# 22_PHY_GE_PP1.net
KiCad netlist of a schematic drawn in Altium Designer
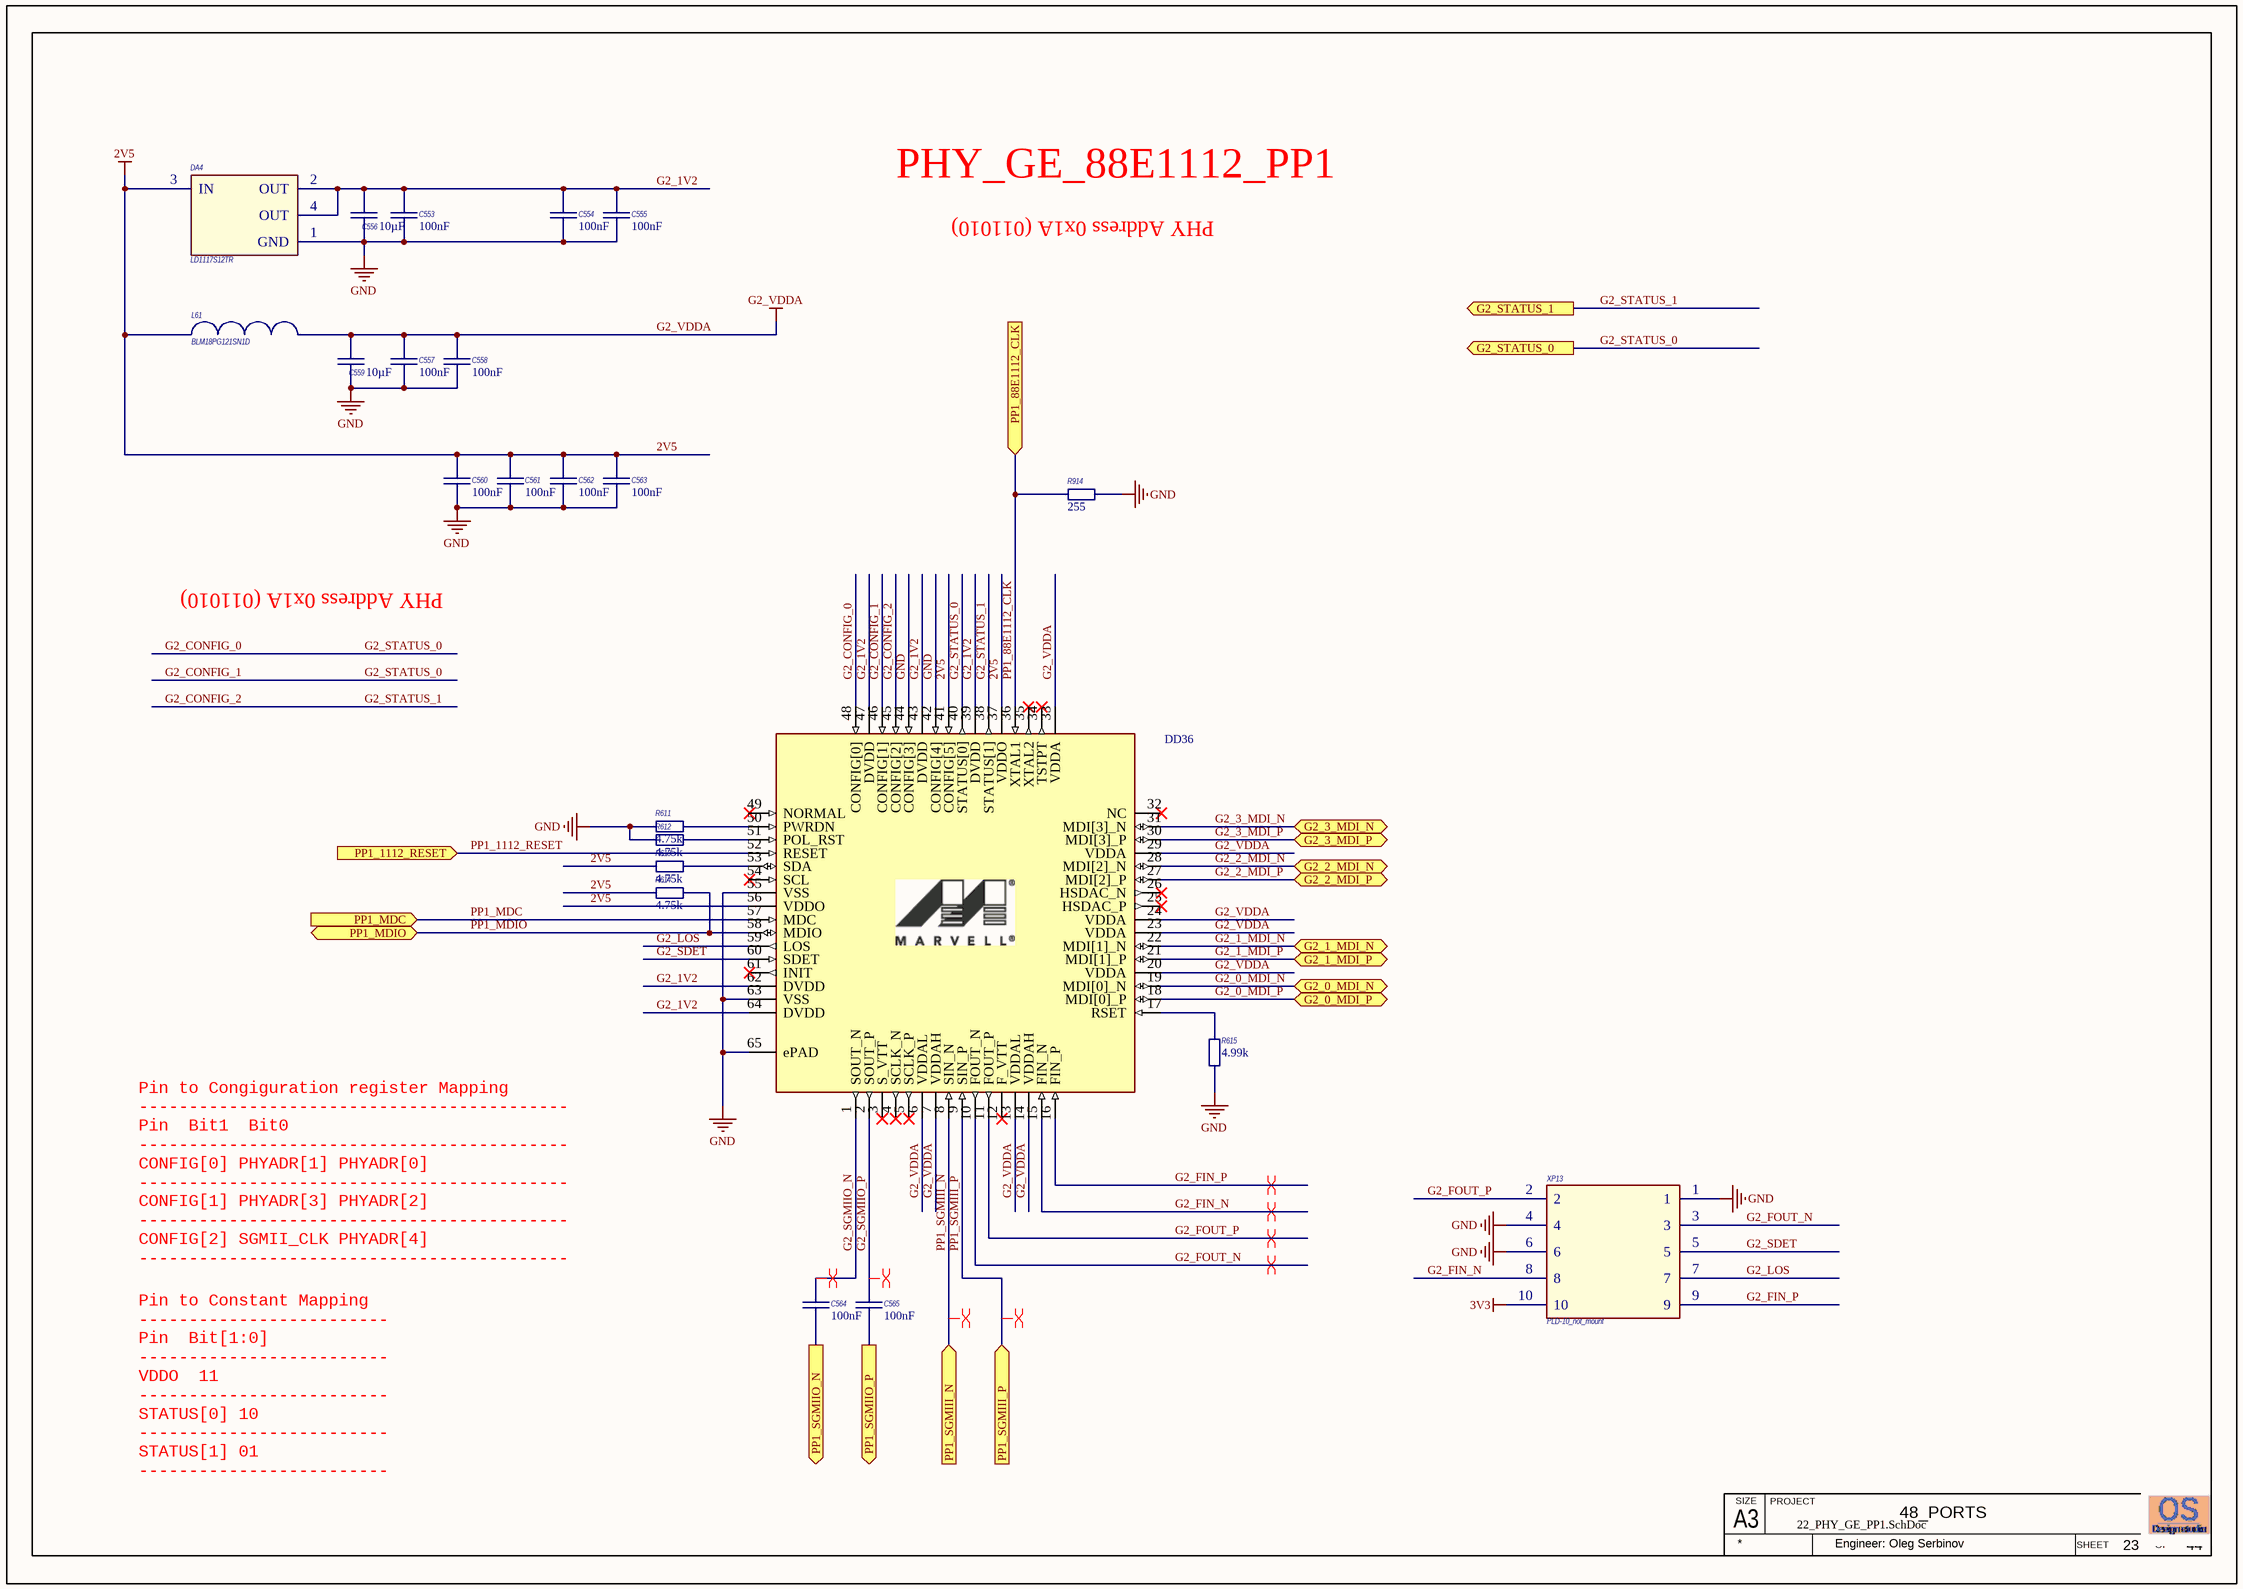
[diagram p0: 22_PHY_GE_PP1.SchDoc]

(export (version "E")
  (design (tool "Eeschema 10.0.6"))
  (components
    (comp (ref "C553")
      (value "GRM155R71E104KE14D")
      (footprint "C0402_IPC High Density")
      (description "C0402, 100nF, 25V, X7R")
      (fields
        (field (name "MANUFACTURER") "Murata")
        (field (name "CAPACITANCE") "100nF")
        (field (name "CUSTOMER PART NUMBER") "Конденсатор, 100n, 0402, 25V, X7R, 10%")
      )
      (libsource (lib "CAPACITORS") (part "GRM155R71E104KE14D"))
    )
    (comp (ref "C554")
      (value "GRM155R71E104KE14D")
      (footprint "C0402_IPC High Density")
      (description "C0402, 100nF, 25V, X7R")
      (fields
        (field (name "MANUFACTURER") "Murata")
        (field (name "CAPACITANCE") "100nF")
        (field (name "CUSTOMER PART NUMBER") "Конденсатор, 100n, 0402, 25V, X7R, 10%")
      )
      (libsource (lib "CAPACITORS") (part "GRM155R71E104KE14D"))
    )
    (comp (ref "C555")
      (value "GRM155R71E104KE14D")
      (footprint "C0402_IPC High Density")
      (description "C0402, 100nF, 25V, X7R")
      (fields
        (field (name "MANUFACTURER") "Murata")
        (field (name "CAPACITANCE") "100nF")
        (field (name "CUSTOMER PART NUMBER") "Конденсатор, 100n, 0402, 25V, X7R, 10%")
      )
      (libsource (lib "CAPACITORS") (part "GRM155R71E104KE14D"))
    )
    (comp (ref "C556")
      (value "GRM21BR61C106KE15")
      (footprint "CAPC2012[0805]")
      (description "C0805, 10uF 10%, 16V, X5R")
      (fields
        (field (name "MANUFACTURER") "Murata")
        (field (name "TOLERANCE") "±10%")
        (field (name "CAPACITANCE") "10µF")
      )
      (libsource (lib "CAPACITORS") (part "GRM21BR61C106KE15"))
    )
    (comp (ref "C557")
      (value "GRM155R71E104KE14D")
      (footprint "C0402_IPC High Density")
      (description "C0402, 100nF, 25V, X7R")
      (fields
        (field (name "MANUFACTURER") "Murata")
        (field (name "CAPACITANCE") "100nF")
        (field (name "CUSTOMER PART NUMBER") "Конденсатор, 100n, 0402, 25V, X7R, 10%")
      )
      (libsource (lib "CAPACITORS") (part "GRM155R71E104KE14D"))
    )
    (comp (ref "C558")
      (value "GRM155R71E104KE14D")
      (footprint "C0402_IPC High Density")
      (description "C0402, 100nF, 25V, X7R")
      (fields
        (field (name "MANUFACTURER") "Murata")
        (field (name "CAPACITANCE") "100nF")
        (field (name "CUSTOMER PART NUMBER") "Конденсатор, 100n, 0402, 25V, X7R, 10%")
      )
      (libsource (lib "CAPACITORS") (part "GRM155R71E104KE14D"))
    )
    (comp (ref "C559")
      (value "GRM21BR61C106KE15")
      (footprint "CAPC2012[0805]")
      (description "C0805, 10uF 10%, 16V, X5R")
      (fields
        (field (name "MANUFACTURER") "Murata")
        (field (name "TOLERANCE") "±10%")
        (field (name "CAPACITANCE") "10µF")
      )
      (libsource (lib "CAPACITORS") (part "GRM21BR61C106KE15"))
    )
    (comp (ref "C560")
      (value "GRM155R71E104KE14D")
      (footprint "C0402_IPC High Density")
      (description "C0402, 100nF, 25V, X7R")
      (fields
        (field (name "MANUFACTURER") "Murata")
        (field (name "CAPACITANCE") "100nF")
        (field (name "CUSTOMER PART NUMBER") "Конденсатор, 100n, 0402, 25V, X7R, 10%")
      )
      (libsource (lib "CAPACITORS") (part "GRM155R71E104KE14D"))
    )
    (comp (ref "C561")
      (value "GRM155R71E104KE14D")
      (footprint "C0402_IPC High Density")
      (description "C0402, 100nF, 25V, X7R")
      (fields
        (field (name "MANUFACTURER") "Murata")
        (field (name "CAPACITANCE") "100nF")
        (field (name "CUSTOMER PART NUMBER") "Конденсатор, 100n, 0402, 25V, X7R, 10%")
      )
      (libsource (lib "CAPACITORS") (part "GRM155R71E104KE14D"))
    )
    (comp (ref "C562")
      (value "GRM155R71E104KE14D")
      (footprint "C0402_IPC High Density")
      (description "C0402, 100nF, 25V, X7R")
      (fields
        (field (name "MANUFACTURER") "Murata")
        (field (name "CAPACITANCE") "100nF")
        (field (name "CUSTOMER PART NUMBER") "Конденсатор, 100n, 0402, 25V, X7R, 10%")
      )
      (libsource (lib "CAPACITORS") (part "GRM155R71E104KE14D"))
    )
    (comp (ref "C563")
      (value "GRM155R71E104KE14D")
      (footprint "C0402_IPC High Density")
      (description "C0402, 100nF, 25V, X7R")
      (fields
        (field (name "MANUFACTURER") "Murata")
        (field (name "CAPACITANCE") "100nF")
        (field (name "CUSTOMER PART NUMBER") "Конденсатор, 100n, 0402, 25V, X7R, 10%")
      )
      (libsource (lib "CAPACITORS") (part "GRM155R71E104KE14D"))
    )
    (comp (ref "C564")
      (value "GRM155R71E104KE14D")
      (footprint "C0402_IPC High Density")
      (description "C0402, 100nF, 25V, X7R")
      (fields
        (field (name "MANUFACTURER") "Murata")
        (field (name "CAPACITANCE") "100nF")
        (field (name "CUSTOMER PART NUMBER") "Конденсатор, 100n, 0402, 25V, X7R, 10%")
      )
      (libsource (lib "CAPACITORS") (part "GRM155R71E104KE14D"))
    )
    (comp (ref "C565")
      (value "GRM155R71E104KE14D")
      (footprint "C0402_IPC High Density")
      (description "C0402, 100nF, 25V, X7R")
      (fields
        (field (name "MANUFACTURER") "Murata")
        (field (name "CAPACITANCE") "100nF")
        (field (name "CUSTOMER PART NUMBER") "Конденсатор, 100n, 0402, 25V, X7R, 10%")
      )
      (libsource (lib "CAPACITORS") (part "GRM155R71E104KE14D"))
    )
    (comp (ref "DA4")
      (value "LD1117S12TR")
      (footprint "SOT223_N")
      (description "IC REG LDO 0.8A 1.2V SOT223-4")
      (fields
        (field (name "MANUFACTURER PART NUMBER") "LD1117S-12TR")
        (field (name "MANUFACTURER") "STMicroelectronics")
      )
      (libsource (lib "DIGITAL and ANALIG ICs") (part "LD1117S12TR"))
    )
    (comp (ref "DD36")
      (value "88E1112-C2-NNC1")
      (footprint "QFN50P900X900X100-64N")
      (description "IC GIGABIT PHY with Dual SGMII, 64-QFN Package; Manufacturer: Marvell")
      (fields
        (field (name "MANUFACTURER") "Marvell Technology Group")
        (field (name "CUSTOMER PART NUMBER") "Микросхема, 88E1112-C2-NNC1, IC GIGABIT PHY with Dual SGMII, 64-QFN")
      )
      (libsource (lib "DIGITAL and ANALIG ICs") (part "88E1112-C2-NNC1"))
    )
    (comp (ref "L61")
      (value "BLM18PG121SN1D")
      (footprint "INDC1608X95N")
      (description "FILTER BLM18 (0603, 2A)")
      (fields
        (field (name "MANUFACTURER") "Murata")
        (field (name "RPART NUMBER") "MPZ1608S121ATAH0 ; CIC10P121NC ; MPZ1608S121ATDH5 ; BLM18PG121SH1D ; 742792625")
      )
      (libsource (lib "INDUCTORS") (part "BLM18PG121SN1D"))
    )
    (comp (ref "R611")
      (value "ERJ-2RKF4751X")
      (footprint "R0402_IPC High Density")
      (description "R0402, 4.75k 1%")
      (fields
        (field (name "TOLERANCE") "±1%")
        (field (name "MANUFACTURER") "Panasonic")
        (field (name "RESISTANCE (OHMS)") "4.75k")
      )
      (libsource (lib "RESISTOR") (part "ERJ-2RKF4751X"))
    )
    (comp (ref "R612")
      (value "ERJ-2RKF4751X")
      (footprint "R0402_IPC High Density")
      (description "R0402, 4.75k 1%")
      (fields
        (field (name "TOLERANCE") "±1%")
        (field (name "MANUFACTURER") "Panasonic")
        (field (name "RESISTANCE (OHMS)") "4.75k")
      )
      (libsource (lib "RESISTOR") (part "ERJ-2RKF4751X"))
    )
    (comp (ref "R613")
      (value "ERJ-2RKF4751X")
      (footprint "R0402_IPC High Density")
      (description "R0402, 4.75k 1%")
      (fields
        (field (name "TOLERANCE") "±1%")
        (field (name "MANUFACTURER") "Panasonic")
        (field (name "RESISTANCE (OHMS)") "4.75k")
      )
      (libsource (lib "RESISTOR") (part "ERJ-2RKF4751X"))
    )
    (comp (ref "R614")
      (value "ERJ-2RKF4751X")
      (footprint "R0402_IPC High Density")
      (description "R0402, 4.75k 1%")
      (fields
        (field (name "TOLERANCE") "±1%")
        (field (name "MANUFACTURER") "Panasonic")
        (field (name "RESISTANCE (OHMS)") "4.75k")
      )
      (libsource (lib "RESISTOR") (part "ERJ-2RKF4751X"))
    )
    (comp (ref "R615")
      (value "ERJ-2RKF4991X")
      (footprint "R0402_IPC High Density")
      (description "R0402, 4.99k 1%")
      (fields
        (field (name "TOLERANCE") "±1%")
        (field (name "MANUFACTURER") "Panasonic")
        (field (name "RESISTANCE (OHMS)") "4.99k")
      )
      (libsource (lib "RESISTOR") (part "ERJ-2RKF4991X"))
    )
    (comp (ref "R914")
      (value "ERJ-2RKF2550X")
      (footprint "RESC1005[0402]")
      (description "R0402, 255R 1%")
      (fields
        (field (name "TOLERANCE") "±1%")
        (field (name "MANUFACTURER") "Panasonic")
        (field (name "RESISTANCE (OHMS)") "255")
      )
      (libsource (lib "RESISTOR") (part "ERJ-2RKF2550X"))
    )
    (comp (ref "XP13")
      (value "PLD-10_not_mount")
      (footprint "PLD-10_not_mount")
      (description "Connector PLD-10_not_mount")
      (fields
        (field (name "CUSTOMER PART NUMBER") "Разъем, PLD-10, 10 Positions Header Shrouded Connector 2.54mm Through Hole Gold")
      )
      (libsource (lib "CONNECTORS") (part "PLD-10_not_mount"))
    )
  )
  (nets
    (net (code "1") (name "/G2_0_MDI_N") (class "Default")
      (node (ref "DD36") (pin "19") (pinfunction "MDI[0]_N_19") (pintype "bidirectional"))
    )
    (net (code "2") (name "/G2_0_MDI_P") (class "Default")
      (node (ref "DD36") (pin "18") (pinfunction "MDI[0]_P_18") (pintype "bidirectional"))
    )
    (net (code "3") (name "/G2_1V2") (class "Default")
      (node (ref "C553") (pin "2") (pintype "passive"))
      (node (ref "C554") (pin "2") (pintype "passive"))
      (node (ref "C555") (pin "2") (pintype "passive"))
      (node (ref "C556") (pin "2") (pintype "passive"))
      (node (ref "DA4") (pin "2") (pinfunction "OUT_2") (pintype "passive"))
      (node (ref "DA4") (pin "4") (pinfunction "OUT_4") (pintype "passive"))
      (node (ref "DD36") (pin "39") (pinfunction "DVDD_39") (pintype "power_in"))
      (node (ref "DD36") (pin "43") (pinfunction "DVDD_43") (pintype "power_in"))
      (node (ref "DD36") (pin "47") (pinfunction "DVDD_47") (pintype "power_in"))
      (node (ref "DD36") (pin "62") (pinfunction "DVDD_62") (pintype "power_in"))
      (node (ref "DD36") (pin "64") (pinfunction "DVDD_64") (pintype "power_in"))
    )
    (net (code "4") (name "/G2_1_MDI_N") (class "Default")
      (node (ref "DD36") (pin "22") (pinfunction "MDI[1]_N_22") (pintype "bidirectional"))
    )
    (net (code "5") (name "/G2_1_MDI_P") (class "Default")
      (node (ref "DD36") (pin "21") (pinfunction "MDI[1]_P_21") (pintype "bidirectional"))
    )
    (net (code "6") (name "/G2_2_MDI_N") (class "Default")
      (node (ref "DD36") (pin "28") (pinfunction "MDI[2]_N_28") (pintype "bidirectional"))
    )
    (net (code "7") (name "/G2_2_MDI_P") (class "Default")
      (node (ref "DD36") (pin "27") (pinfunction "MDI[2]_P_27") (pintype "bidirectional"))
    )
    (net (code "8") (name "/G2_3_MDI_N") (class "Default")
      (node (ref "DD36") (pin "31") (pinfunction "MDI[3]_N_31") (pintype "bidirectional"))
    )
    (net (code "9") (name "/G2_3_MDI_P") (class "Default")
      (node (ref "DD36") (pin "30") (pinfunction "MDI[3]_P_30") (pintype "bidirectional"))
    )
    (net (code "10") (name "/G2_CONFIG_0") (class "Default")
      (node (ref "DD36") (pin "40") (pinfunction "STATUS[0]_40") (pintype "output"))
      (node (ref "DD36") (pin "46") (pinfunction "CONFIG[1]_46") (pintype "input"))
      (node (ref "DD36") (pin "48") (pinfunction "CONFIG[0]_48") (pintype "input"))
    )
    (net (code "11") (name "/G2_CONFIG_2") (class "Default")
      (node (ref "DD36") (pin "38") (pinfunction "STATUS[1]_38") (pintype "output"))
      (node (ref "DD36") (pin "45") (pinfunction "CONFIG[2]_45") (pintype "input"))
    )
    (net (code "12") (name "/G2_FIN_N") (class "Default")
      (node (ref "DD36") (pin "15") (pinfunction "FIN_N_15") (pintype "input"))
      (node (ref "XP13") (pin "8") (pinfunction "8_8") (pintype "passive"))
    )
    (net (code "13") (name "/G2_FIN_P") (class "Default")
      (node (ref "DD36") (pin "16") (pinfunction "FIN_P_16") (pintype "input"))
      (node (ref "XP13") (pin "9") (pinfunction "9_9") (pintype "passive"))
    )
    (net (code "14") (name "/G2_FOUT_N") (class "Default")
      (node (ref "DD36") (pin "10") (pinfunction "FOUT_N_10") (pintype "output"))
      (node (ref "XP13") (pin "3") (pinfunction "3_3") (pintype "passive"))
    )
    (net (code "15") (name "/G2_FOUT_P") (class "Default")
      (node (ref "DD36") (pin "11") (pinfunction "FOUT_P_11") (pintype "output"))
      (node (ref "XP13") (pin "2") (pinfunction "2_2") (pintype "passive"))
    )
    (net (code "16") (name "/G2_LOS") (class "Default")
      (node (ref "DD36") (pin "59") (pinfunction "LOS_59") (pintype "output"))
      (node (ref "XP13") (pin "7") (pinfunction "7_7") (pintype "passive"))
    )
    (net (code "17") (name "/G2_SDET") (class "Default")
      (node (ref "DD36") (pin "60") (pinfunction "SDET_60") (pintype "input"))
      (node (ref "XP13") (pin "5") (pinfunction "5_5") (pintype "passive"))
    )
    (net (code "18") (name "/G2_SGMIIO_N") (class "Default")
      (node (ref "C564") (pin "1") (pintype "passive"))
      (node (ref "DD36") (pin "1") (pinfunction "SOUT_N_1") (pintype "output"))
    )
    (net (code "19") (name "/G2_SGMIIO_P") (class "Default")
      (node (ref "C565") (pin "1") (pintype "passive"))
      (node (ref "DD36") (pin "2") (pinfunction "SOUT_P_2") (pintype "output"))
    )
    (net (code "20") (name "/PP1_88E1112_CLK") (class "Default")
      (node (ref "DD36") (pin "36") (pinfunction "XTAL1_36") (pintype "input"))
      (node (ref "R914") (pin "2") (pintype "passive"))
    )
    (net (code "21") (name "/PP1_1112_RESET") (class "Default")
      (node (ref "DD36") (pin "52") (pinfunction "RESET_52") (pintype "input"))
    )
    (net (code "22") (name "/PP1_MDC") (class "Default")
      (node (ref "DD36") (pin "57") (pinfunction "MDC_57") (pintype "input"))
    )
    (net (code "23") (name "/PP1_MDIO") (class "Default")
      (node (ref "DD36") (pin "58") (pinfunction "MDIO_58") (pintype "bidirectional"))
      (node (ref "R614") (pin "2") (pintype "passive"))
    )
    (net (code "24") (name "/PP1_SGMIII_N") (class "Default")
      (node (ref "DD36") (pin "8") (pinfunction "SIN_N_8") (pintype "input"))
    )
    (net (code "25") (name "/PP1_SGMIII_P") (class "Default")
      (node (ref "DD36") (pin "9") (pinfunction "SIN_P_9") (pintype "input"))
    )
    (net (code "26") (name "/PP1_SGMIIO_N") (class "Default")
      (node (ref "C564") (pin "2") (pintype "passive"))
    )
    (net (code "27") (name "/PP1_SGMIIO_P") (class "Default")
      (node (ref "C565") (pin "2") (pintype "passive"))
    )
    (net (code "28") (name "2V5") (class "Default")
      (node (ref "C560") (pin "2") (pintype "passive"))
      (node (ref "C561") (pin "2") (pintype "passive"))
      (node (ref "C562") (pin "2") (pintype "passive"))
      (node (ref "C563") (pin "2") (pintype "passive"))
      (node (ref "DA4") (pin "3") (pinfunction "IN_3") (pintype "passive"))
      (node (ref "DD36") (pin "37") (pinfunction "VDDO_37") (pintype "passive"))
      (node (ref "DD36") (pin "41") (pinfunction "CONFIG[5]_41") (pintype "input"))
      (node (ref "DD36") (pin "56") (pinfunction "VDDO_56") (pintype "passive"))
      (node (ref "L61") (pin "1") (pinfunction "1_1") (pintype "passive"))
      (node (ref "R613") (pin "1") (pintype "passive"))
      (node (ref "R614") (pin "1") (pintype "passive"))
    )
    (net (code "29") (name "3V3") (class "Default")
      (node (ref "XP13") (pin "10") (pinfunction "10_10") (pintype "passive"))
    )
    (net (code "30") (name "G2_VDDA") (class "Default")
      (node (ref "C557") (pin "2") (pintype "passive"))
      (node (ref "C558") (pin "2") (pintype "passive"))
      (node (ref "C559") (pin "2") (pintype "passive"))
      (node (ref "DD36") (pin "13") (pinfunction "VDDAL_13") (pintype "power_in"))
      (node (ref "DD36") (pin "14") (pinfunction "VDDAH_14") (pintype "power_in"))
      (node (ref "DD36") (pin "20") (pinfunction "VDDA_20") (pintype "power_in"))
      (node (ref "DD36") (pin "23") (pinfunction "VDDA_23") (pintype "power_in"))
      (node (ref "DD36") (pin "24") (pinfunction "VDDA_24") (pintype "power_in"))
      (node (ref "DD36") (pin "29") (pinfunction "VDDA_29") (pintype "power_in"))
      (node (ref "DD36") (pin "33") (pinfunction "VDDA_33") (pintype "power_in"))
      (node (ref "DD36") (pin "6") (pinfunction "VDDAL_6") (pintype "power_in"))
      (node (ref "DD36") (pin "7") (pinfunction "VDDAH_7") (pintype "power_in"))
      (node (ref "L61") (pin "2") (pinfunction "2_2") (pintype "passive"))
    )
    (net (code "31") (name "GND") (class "Default")
      (node (ref "C553") (pin "1") (pintype "passive"))
      (node (ref "C554") (pin "1") (pintype "passive"))
      (node (ref "C555") (pin "1") (pintype "passive"))
      (node (ref "C556") (pin "1") (pintype "passive"))
      (node (ref "C557") (pin "1") (pintype "passive"))
      (node (ref "C558") (pin "1") (pintype "passive"))
      (node (ref "C559") (pin "1") (pintype "passive"))
      (node (ref "C560") (pin "1") (pintype "passive"))
      (node (ref "C561") (pin "1") (pintype "passive"))
      (node (ref "C562") (pin "1") (pintype "passive"))
      (node (ref "C563") (pin "1") (pintype "passive"))
      (node (ref "DA4") (pin "1") (pinfunction "GND_1") (pintype "power_in"))
      (node (ref "DD36") (pin "42") (pinfunction "CONFIG[4]_42") (pintype "input"))
      (node (ref "DD36") (pin "44") (pinfunction "CONFIG[3]_44") (pintype "input"))
      (node (ref "DD36") (pin "55") (pinfunction "VSS_55") (pintype "power_in"))
      (node (ref "DD36") (pin "63") (pinfunction "VSS_63") (pintype "power_in"))
      (node (ref "DD36") (pin "65") (pinfunction "ePAD_65") (pintype "power_in"))
      (node (ref "R611") (pin "1") (pintype "passive"))
      (node (ref "R612") (pin "1") (pintype "passive"))
      (node (ref "R615") (pin "1") (pintype "passive"))
      (node (ref "R914") (pin "1") (pintype "passive"))
      (node (ref "XP13") (pin "1") (pinfunction "1_1") (pintype "passive"))
      (node (ref "XP13") (pin "4") (pinfunction "4_4") (pintype "passive"))
      (node (ref "XP13") (pin "6") (pinfunction "6_6") (pintype "passive"))
    )
    (net (code "32") (name "Net-(DD36-POL_RST)") (class "Default")
      (node (ref "DD36") (pin "51") (pinfunction "POL_RST_51") (pintype "input"))
      (node (ref "R612") (pin "2") (pintype "passive"))
    )
    (net (code "33") (name "Net-(DD36-PWRDN)") (class "Default")
      (node (ref "DD36") (pin "50") (pinfunction "PWRDN_50") (pintype "input"))
      (node (ref "R611") (pin "2") (pintype "passive"))
    )
    (net (code "34") (name "Net-(DD36-RSET)") (class "Default")
      (node (ref "DD36") (pin "17") (pinfunction "RSET_17") (pintype "input"))
      (node (ref "R615") (pin "2") (pintype "passive"))
    )
    (net (code "35") (name "Net-(DD36-SDA)") (class "Default")
      (node (ref "DD36") (pin "53") (pinfunction "SDA_53") (pintype "bidirectional"))
      (node (ref "R613") (pin "2") (pintype "passive"))
    )
    (net (code "36") (name "unconnected-(DD36-F_VTT-Pad12)") (class "Default")
      (node (ref "DD36") (pin "12") (pinfunction "F_VTT_12") (pintype "power_in+no_connect"))
    )
    (net (code "37") (name "unconnected-(DD36-HSDAC_N-Pad26)") (class "Default")
      (node (ref "DD36") (pin "26") (pinfunction "HSDAC_N_26") (pintype "output+no_connect"))
    )
    (net (code "38") (name "unconnected-(DD36-HSDAC_P-Pad25)") (class "Default")
      (node (ref "DD36") (pin "25") (pinfunction "HSDAC_P_25") (pintype "output+no_connect"))
    )
    (net (code "39") (name "unconnected-(DD36-INIT-Pad61)") (class "Default")
      (node (ref "DD36") (pin "61") (pinfunction "INIT_61") (pintype "output+no_connect"))
    )
    (net (code "40") (name "unconnected-(DD36-NC-Pad32)") (class "Default")
      (node (ref "DD36") (pin "32") (pinfunction "NC_32") (pintype "passive+no_connect"))
    )
    (net (code "41") (name "unconnected-(DD36-NORMAL-Pad49)") (class "Default")
      (node (ref "DD36") (pin "49") (pinfunction "NORMAL_49") (pintype "input+no_connect"))
    )
    (net (code "42") (name "unconnected-(DD36-SCL-Pad54)") (class "Default")
      (node (ref "DD36") (pin "54") (pinfunction "SCL_54") (pintype "input+no_connect"))
    )
    (net (code "43") (name "unconnected-(DD36-SCLK_N-Pad4)") (class "Default")
      (node (ref "DD36") (pin "4") (pinfunction "SCLK_N_4") (pintype "output+no_connect"))
    )
    (net (code "44") (name "unconnected-(DD36-SCLK_P-Pad5)") (class "Default")
      (node (ref "DD36") (pin "5") (pinfunction "SCLK_P_5") (pintype "output+no_connect"))
    )
    (net (code "45") (name "unconnected-(DD36-S_VTT-Pad3)") (class "Default")
      (node (ref "DD36") (pin "3") (pinfunction "S_VTT_3") (pintype "power_in+no_connect"))
    )
    (net (code "46") (name "unconnected-(DD36-TSTPT-Pad34)") (class "Default")
      (node (ref "DD36") (pin "34") (pinfunction "TSTPT_34") (pintype "output+no_connect"))
    )
    (net (code "47") (name "unconnected-(DD36-XTAL2-Pad35)") (class "Default")
      (node (ref "DD36") (pin "35") (pinfunction "XTAL2_35") (pintype "output+no_connect"))
    )
  )
)
